# Core_Shield_Shield.net
KiCad netlist of a schematic drawn in EAGLE
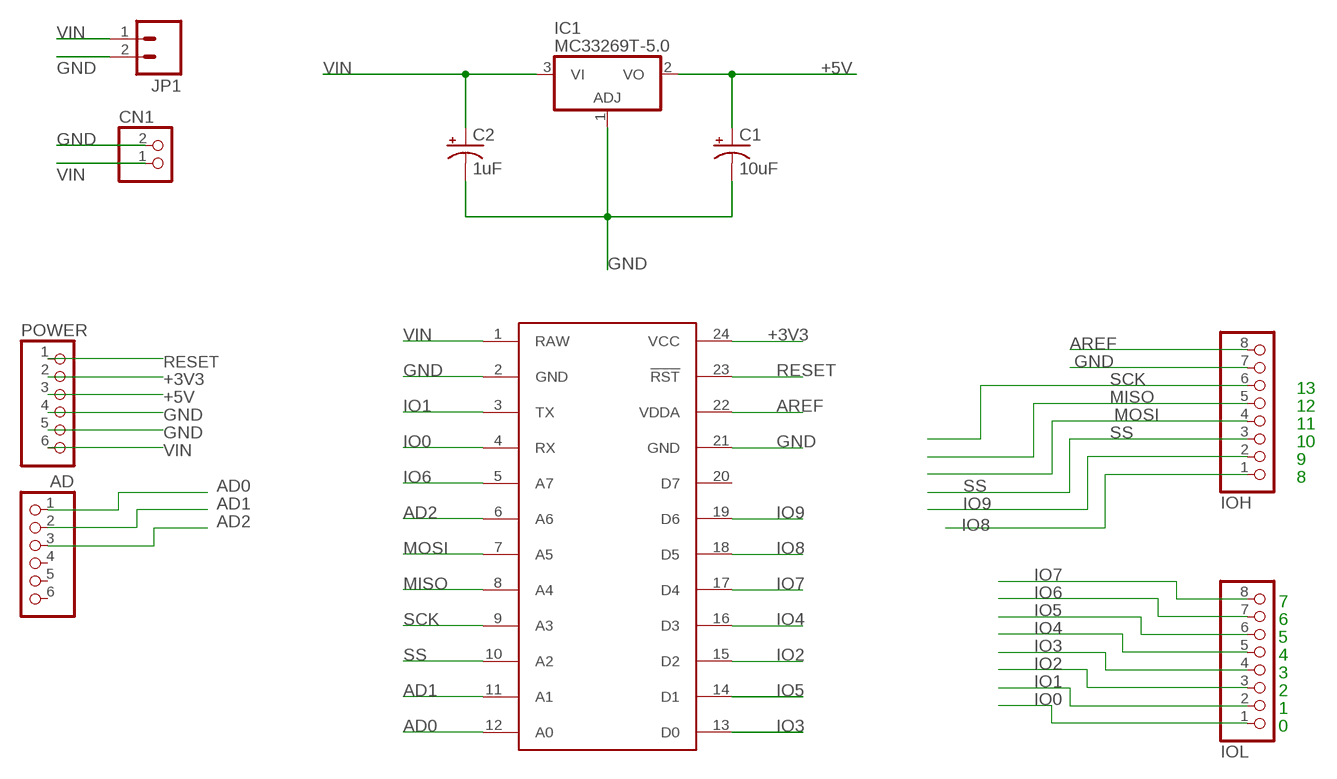
[diagram p0: schematic, sheet 1]

(export (version "E")
  (design (tool "Eeschema 10.0.6"))
  (components
    (comp (ref "AD")
      (value "PINHD-1X6")
      (footprint "eagle-import:1X06")
      (libsource (lib "eagle-import") (part "PINHD-1X6"))
    )
    (comp (ref "C1")
      (value "10uF")
      (footprint "eagle-import:CPOL-RADIAL-10UF-25V")
      (libsource (lib "eagle-import") (part "CAP_POLPTH2"))
    )
    (comp (ref "C2")
      (value "1uF")
      (footprint "eagle-import:CPOL-RADIAL-10UF-25V")
      (libsource (lib "eagle-import") (part "CAP_POLPTH2"))
    )
    (comp (ref "CN1")
      (value "JST_2PIN-THM")
      (footprint "eagle-import:JST-PH-2-THM")
      (libsource (lib "eagle-import") (part "JST_2PIN-THM"))
    )
    (comp (ref "IC1")
      (value "MC33269T-5.0")
      (footprint "eagle-import:TO220V")
      (libsource (lib "eagle-import") (part "MC33269?T-5.0"))
    )
    (comp (ref "IOH")
      (value "PINHD-1X8")
      (footprint "eagle-import:1X08")
      (libsource (lib "eagle-import") (part "PINHD-1X8"))
    )
    (comp (ref "IOL")
      (value "PINHD-1X8")
      (footprint "eagle-import:1X08")
      (libsource (lib "eagle-import") (part "PINHD-1X8"))
    )
    (comp (ref "JP1")
      (value "M02LOCK")
      (footprint "eagle-import:1X02_LOCK")
      (libsource (lib "eagle-import") (part "M02LOCK"))
    )
    (comp (ref "POWER")
      (value "PINHD-1X6")
      (footprint "eagle-import:1X06")
      (libsource (lib "eagle-import") (part "PINHD-1X6"))
    )
    (comp (ref "U$1")
      (value "SPARK_CORECORE")
      (footprint "eagle-import:SPARK_CORE")
      (libsource (lib "eagle-import") (part "SPARK_CORECORE"))
    )
  )
  (nets
    (net (code "1") (name "/+3V3") (class "Default")
      (node (ref "POWER") (pin "2") (pinfunction "2_2") (pintype "passive"))
      (node (ref "U$1") (pin "24") (pinfunction "VCC_24") (pintype "power_in"))
    )
    (net (code "2") (name "/+5V") (class "Default")
      (node (ref "C1") (pin "1") (pinfunction "+_1") (pintype "passive"))
      (node (ref "IC1") (pin "2") (pinfunction "VO_2") (pintype "passive"))
      (node (ref "POWER") (pin "3") (pinfunction "3_3") (pintype "passive"))
    )
    (net (code "3") (name "/AD0") (class "Default")
      (node (ref "AD") (pin "1") (pinfunction "1_1") (pintype "passive"))
      (node (ref "U$1") (pin "12") (pinfunction "A0_12") (pintype "bidirectional"))
    )
    (net (code "4") (name "/AD1") (class "Default")
      (node (ref "AD") (pin "2") (pinfunction "2_2") (pintype "passive"))
      (node (ref "U$1") (pin "11") (pinfunction "A1_11") (pintype "bidirectional"))
    )
    (net (code "5") (name "/AD2") (class "Default")
      (node (ref "AD") (pin "3") (pinfunction "3_3") (pintype "passive"))
      (node (ref "U$1") (pin "6") (pinfunction "A6_6") (pintype "bidirectional"))
    )
    (net (code "6") (name "/AREF") (class "Default")
      (node (ref "IOH") (pin "8") (pinfunction "8_8") (pintype "passive"))
      (node (ref "U$1") (pin "22") (pinfunction "VDDA_22") (pintype "power_in"))
    )
    (net (code "7") (name "/GND") (class "Default")
      (node (ref "C1") (pin "2") (pinfunction "-_2") (pintype "passive"))
      (node (ref "C2") (pin "2") (pinfunction "-_2") (pintype "passive"))
      (node (ref "CN1") (pin "2") (pinfunction "1_2") (pintype "passive"))
      (node (ref "IC1") (pin "1") (pinfunction "ADJ_1") (pintype "input"))
      (node (ref "IOH") (pin "7") (pinfunction "7_7") (pintype "passive"))
      (node (ref "JP1") (pin "2") (pinfunction "2_2") (pintype "passive"))
      (node (ref "POWER") (pin "4") (pinfunction "4_4") (pintype "passive"))
      (node (ref "POWER") (pin "5") (pinfunction "5_5") (pintype "passive"))
      (node (ref "U$1") (pin "2") (pinfunction "GND_2") (pintype "power_in"))
      (node (ref "U$1") (pin "21") (pinfunction "GND_21") (pintype "power_in"))
    )
    (net (code "8") (name "/IO0") (class "Default")
      (node (ref "IOL") (pin "1") (pinfunction "1_1") (pintype "passive"))
      (node (ref "U$1") (pin "4") (pinfunction "RX_4") (pintype "bidirectional"))
    )
    (net (code "9") (name "/IO1") (class "Default")
      (node (ref "IOL") (pin "2") (pinfunction "2_2") (pintype "passive"))
      (node (ref "U$1") (pin "3") (pinfunction "TX_3") (pintype "bidirectional"))
    )
    (net (code "10") (name "/IO2") (class "Default")
      (node (ref "IOL") (pin "3") (pinfunction "3_3") (pintype "passive"))
      (node (ref "U$1") (pin "15") (pinfunction "D2_15") (pintype "bidirectional"))
    )
    (net (code "11") (name "/IO3") (class "Default")
      (node (ref "IOL") (pin "4") (pinfunction "4_4") (pintype "passive"))
      (node (ref "U$1") (pin "13") (pinfunction "D0_13") (pintype "bidirectional"))
    )
    (net (code "12") (name "/IO4") (class "Default")
      (node (ref "IOL") (pin "5") (pinfunction "5_5") (pintype "passive"))
      (node (ref "U$1") (pin "16") (pinfunction "D3_16") (pintype "bidirectional"))
    )
    (net (code "13") (name "/IO5") (class "Default")
      (node (ref "IOL") (pin "6") (pinfunction "6_6") (pintype "passive"))
      (node (ref "U$1") (pin "14") (pinfunction "D1_14") (pintype "bidirectional"))
    )
    (net (code "14") (name "/IO6") (class "Default")
      (node (ref "IOL") (pin "7") (pinfunction "7_7") (pintype "passive"))
      (node (ref "U$1") (pin "5") (pinfunction "A7_5") (pintype "bidirectional"))
    )
    (net (code "15") (name "/IO7") (class "Default")
      (node (ref "IOL") (pin "8") (pinfunction "8_8") (pintype "passive"))
      (node (ref "U$1") (pin "17") (pinfunction "D4_17") (pintype "bidirectional"))
    )
    (net (code "16") (name "/IO8") (class "Default")
      (node (ref "IOH") (pin "1") (pinfunction "1_1") (pintype "passive"))
      (node (ref "U$1") (pin "18") (pinfunction "D5_18") (pintype "bidirectional"))
    )
    (net (code "17") (name "/IO9") (class "Default")
      (node (ref "IOH") (pin "2") (pinfunction "2_2") (pintype "passive"))
      (node (ref "U$1") (pin "19") (pinfunction "D6_19") (pintype "bidirectional"))
    )
    (net (code "18") (name "/MISO") (class "Default")
      (node (ref "IOH") (pin "5") (pinfunction "5_5") (pintype "passive"))
      (node (ref "U$1") (pin "8") (pinfunction "A4_8") (pintype "bidirectional"))
    )
    (net (code "19") (name "/MOSI") (class "Default")
      (node (ref "IOH") (pin "4") (pinfunction "4_4") (pintype "passive"))
      (node (ref "U$1") (pin "7") (pinfunction "A5_7") (pintype "bidirectional"))
    )
    (net (code "20") (name "/RESET") (class "Default")
      (node (ref "POWER") (pin "1") (pinfunction "1_1") (pintype "passive"))
      (node (ref "U$1") (pin "23") (pinfunction "~{RST}_23") (pintype "bidirectional"))
    )
    (net (code "21") (name "/SCK") (class "Default")
      (node (ref "IOH") (pin "6") (pinfunction "6_6") (pintype "passive"))
      (node (ref "U$1") (pin "9") (pinfunction "A3_9") (pintype "bidirectional"))
    )
    (net (code "22") (name "/SS") (class "Default")
      (node (ref "IOH") (pin "3") (pinfunction "3_3") (pintype "passive"))
      (node (ref "U$1") (pin "10") (pinfunction "A2_10") (pintype "bidirectional"))
    )
    (net (code "23") (name "/VIN") (class "Default")
      (node (ref "C2") (pin "1") (pinfunction "+_1") (pintype "passive"))
      (node (ref "CN1") (pin "1") (pinfunction "2_1") (pintype "passive"))
      (node (ref "IC1") (pin "3") (pinfunction "VI_3") (pintype "input"))
      (node (ref "JP1") (pin "1") (pinfunction "1_1") (pintype "passive"))
      (node (ref "POWER") (pin "6") (pinfunction "6_6") (pintype "passive"))
      (node (ref "U$1") (pin "1") (pinfunction "RAW_1") (pintype "power_in"))
    )
    (net (code "24") (name "unconnected-(AD-Pad4)") (class "Default")
      (node (ref "AD") (pin "4") (pinfunction "4_4") (pintype "passive"))
    )
    (net (code "25") (name "unconnected-(AD-Pad5)") (class "Default")
      (node (ref "AD") (pin "5") (pinfunction "5_5") (pintype "passive"))
    )
    (net (code "26") (name "unconnected-(AD-Pad6)") (class "Default")
      (node (ref "AD") (pin "6") (pinfunction "6_6") (pintype "passive"))
    )
    (net (code "27") (name "unconnected-(U$1-D7-Pad20)") (class "Default")
      (node (ref "U$1") (pin "20") (pinfunction "D7_20") (pintype "bidirectional"))
    )
  )
)
